# -_-.net
KiCad netlist of a schematic drawn in Altium Designer
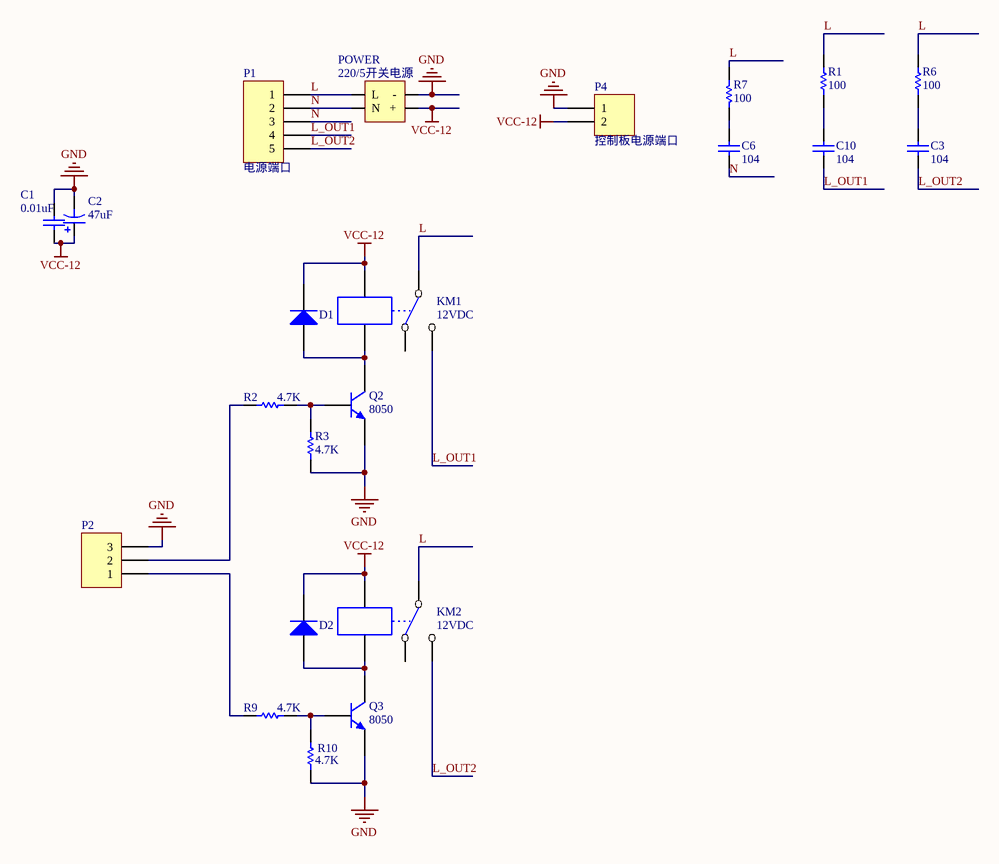
[diagram p0: 智能家居-窗帘-电力板.SchDoc]

(export (version "E")
  (design (tool "Eeschema 10.0.6"))
  (components
    (comp (ref "C1")
      (value "0.01uF")
      (footprint "0.1UF")
      (description "Capacitor")
      (fields (field (name "PUBLISHER") "Altium Limited"))
      (libsource (lib "Miscellaneous Devices") (part "Cap"))
    )
    (comp (ref "C2")
      (value "47uF")
      (footprint "CD5")
      (description "Polarized Capacitor (Radial)")
      (fields (field (name "Comment") "Cap Pol1") (field (name "PUBLISHER") "Altium Limited"))
      (libsource (lib "Miscellaneous Devices") (part "Cap Pol1"))
    )
    (comp (ref "C3")
      (value "104")
      (footprint "0.1UF/275V")
      (description "Capacitor")
      (fields (field (name "Comment") "Cap") (field (name "PUBLISHER") "Altium Limited"))
      (libsource (lib "Miscellaneous Devices") (part "Cap"))
    )
    (comp (ref "C6")
      (value "104")
      (footprint "0.1UF/275V")
      (description "Capacitor")
      (fields (field (name "Comment") "Cap") (field (name "PUBLISHER") "Altium Limited"))
      (libsource (lib "Miscellaneous Devices") (part "Cap"))
    )
    (comp (ref "C10")
      (value "104")
      (footprint "0.1UF/275V")
      (description "Capacitor")
      (fields (field (name "Comment") "Cap") (field (name "PUBLISHER") "Altium Limited"))
      (libsource (lib "Miscellaneous Devices") (part "Cap"))
    )
    (comp (ref "D1")
      (value "Diode")
      (footprint "DIODE")
      (description "Default Diode")
      (fields (field (name "PUBLISHER") "Altium Limited"))
      (libsource (lib "Miscellaneous Devices") (part "Diode"))
    )
    (comp (ref "D2")
      (value "Diode")
      (footprint "DIODE")
      (description "Default Diode")
      (fields (field (name "PUBLISHER") "Altium Limited"))
      (libsource (lib "Miscellaneous Devices") (part "Diode"))
    )
    (comp (ref "KM1") (value "12VDC") (footprint "SRD_RELAY") (libsource (lib "杂项库") (part "SRD-12VDC")))
    (comp (ref "KM2") (value "12VDC") (footprint "SRD_RELAY") (libsource (lib "杂项库") (part "SRD-12VDC")))
    (comp (ref "P1")
      (value "电源端口")
      (footprint "JK128-500-5P")
      (description "Header, 5-Pin")
      (fields (field (name "PUBLISHER") "Altium Limited"))
      (libsource (lib "Miscellaneous Connectors") (part "Header 5"))
    )
    (comp (ref "P2")
      (value "Header 3")
      (footprint "TJC3-3A")
      (description "Header, 3-Pin")
      (fields (field (name "PUBLISHER") "Altium Limited"))
      (libsource (lib "Miscellaneous Connectors") (part "Header 3"))
    )
    (comp (ref "P4")
      (value "控制板电源端口")
      (footprint "TJC3-2A")
      (description "Header, 2-Pin")
      (fields (field (name "PUBLISHER") "Altium Limited"))
      (libsource (lib "Miscellaneous Connectors") (part "Header 2"))
    )
    (comp (ref "POWER")
      (value "220/5开关电源")
      (footprint "220/5开关电源")
      (libsource (lib "杂元件库") (part "220/5开关电源"))
    )
    (comp (ref "Q2")
      (value "8050")
      (footprint "TO-92D")
      (description "NPN Bipolar Transistor")
      (fields (field (name "PUBLISHER") "Altium Limited"))
      (libsource (lib "Miscellaneous Devices") (part "NPN"))
    )
    (comp (ref "Q3")
      (value "8050")
      (footprint "TO-92D")
      (description "NPN Bipolar Transistor")
      (fields (field (name "PUBLISHER") "Altium Limited"))
      (libsource (lib "Miscellaneous Devices") (part "NPN"))
    )
    (comp (ref "R1")
      (value "100")
      (description "Resistor")
      (fields (field (name "PUBLISHER") "Altium Limited"))
      (libsource (lib "Miscellaneous Devices") (part "Res1"))
    )
    (comp (ref "R2")
      (value "4.7K")
      (description "Resistor")
      (fields (field (name "PUBLISHER") "Altium Limited"))
      (libsource (lib "Miscellaneous Devices") (part "Res1"))
    )
    (comp (ref "R3")
      (value "4.7K")
      (description "Resistor")
      (fields (field (name "PUBLISHER") "Altium Limited"))
      (libsource (lib "Miscellaneous Devices") (part "Res1"))
    )
    (comp (ref "R6")
      (value "100")
      (description "Resistor")
      (fields (field (name "PUBLISHER") "Altium Limited"))
      (libsource (lib "Miscellaneous Devices") (part "Res1"))
    )
    (comp (ref "R7")
      (value "100")
      (description "Resistor")
      (fields (field (name "PUBLISHER") "Altium Limited"))
      (libsource (lib "Miscellaneous Devices") (part "Res1"))
    )
    (comp (ref "R9")
      (value "4.7K")
      (description "Resistor")
      (fields (field (name "PUBLISHER") "Altium Limited"))
      (libsource (lib "Miscellaneous Devices") (part "Res1"))
    )
    (comp (ref "R10")
      (value "4.7K")
      (description "Resistor")
      (fields (field (name "PUBLISHER") "Altium Limited"))
      (libsource (lib "Miscellaneous Devices") (part "Res1"))
    )
  )
  (nets
    (net (code "1") (name "/L") (class "Default")
      (node (ref "KM1") (pin "5") (pinfunction "COM_5") (pintype "passive"))
      (node (ref "KM2") (pin "5") (pinfunction "COM_5") (pintype "passive"))
      (node (ref "P1") (pin "1") (pinfunction "1_1") (pintype "passive"))
      (node (ref "POWER") (pin "1") (pinfunction "L_1") (pintype "power_in"))
      (node (ref "R1") (pin "2") (pinfunction "2_2") (pintype "passive"))
      (node (ref "R6") (pin "2") (pinfunction "2_2") (pintype "passive"))
      (node (ref "R7") (pin "1") (pinfunction "1_1") (pintype "passive"))
    )
    (net (code "2") (name "/L_OUT1") (class "Default")
      (node (ref "C10") (pin "1") (pinfunction "1_1") (pintype "passive"))
      (node (ref "KM1") (pin "3") (pinfunction "3_3") (pintype "passive"))
      (node (ref "P1") (pin "4") (pinfunction "4_4") (pintype "passive"))
    )
    (net (code "3") (name "/L_OUT2") (class "Default")
      (node (ref "C3") (pin "1") (pinfunction "1_1") (pintype "passive"))
      (node (ref "KM2") (pin "3") (pinfunction "3_3") (pintype "passive"))
      (node (ref "P1") (pin "5") (pinfunction "5_5") (pintype "passive"))
    )
    (net (code "4") (name "/N") (class "Default")
      (node (ref "C6") (pin "2") (pinfunction "2_2") (pintype "passive"))
      (node (ref "P1") (pin "2") (pinfunction "2_2") (pintype "passive"))
      (node (ref "P1") (pin "3") (pinfunction "3_3") (pintype "passive"))
      (node (ref "POWER") (pin "2") (pinfunction "N_2") (pintype "passive"))
    )
    (net (code "5") (name "GND") (class "Default")
      (node (ref "C1") (pin "2") (pinfunction "2_2") (pintype "passive"))
      (node (ref "C2") (pin "2") (pinfunction "2_2") (pintype "passive"))
      (node (ref "P2") (pin "3") (pinfunction "3_3") (pintype "passive"))
      (node (ref "P4") (pin "1") (pinfunction "1_1") (pintype "passive"))
      (node (ref "POWER") (pin "3") (pinfunction "-_3") (pintype "passive"))
      (node (ref "Q2") (pin "1") (pinfunction "E_1") (pintype "passive"))
      (node (ref "Q3") (pin "1") (pinfunction "E_1") (pintype "passive"))
      (node (ref "R10") (pin "2") (pinfunction "2_2") (pintype "passive"))
      (node (ref "R3") (pin "2") (pinfunction "2_2") (pintype "passive"))
    )
    (net (code "6") (name "Net-(C3-Pad2)") (class "Default")
      (node (ref "C3") (pin "2") (pinfunction "2_2") (pintype "passive"))
      (node (ref "R6") (pin "1") (pinfunction "1_1") (pintype "passive"))
    )
    (net (code "7") (name "Net-(C6-Pad1)") (class "Default")
      (node (ref "C6") (pin "1") (pinfunction "1_1") (pintype "passive"))
      (node (ref "R7") (pin "2") (pinfunction "2_2") (pintype "passive"))
    )
    (net (code "8") (name "Net-(C10-Pad2)") (class "Default")
      (node (ref "C10") (pin "2") (pinfunction "2_2") (pintype "passive"))
      (node (ref "R1") (pin "1") (pinfunction "1_1") (pintype "passive"))
    )
    (net (code "9") (name "Net-(D1-A)") (class "Default")
      (node (ref "D1") (pin "1") (pinfunction "A_1") (pintype "passive"))
      (node (ref "KM1") (pin "4") (pinfunction "4_4") (pintype "passive"))
      (node (ref "Q2") (pin "3") (pinfunction "C_3") (pintype "passive"))
    )
    (net (code "10") (name "Net-(D2-A)") (class "Default")
      (node (ref "D2") (pin "1") (pinfunction "A_1") (pintype "passive"))
      (node (ref "KM2") (pin "4") (pinfunction "4_4") (pintype "passive"))
      (node (ref "Q3") (pin "3") (pinfunction "C_3") (pintype "passive"))
    )
    (net (code "11") (name "Net-(P2-Pad1)") (class "Default")
      (node (ref "P2") (pin "1") (pinfunction "1_1") (pintype "passive"))
      (node (ref "R9") (pin "1") (pinfunction "1_1") (pintype "passive"))
    )
    (net (code "12") (name "Net-(P2-Pad2)") (class "Default")
      (node (ref "P2") (pin "2") (pinfunction "2_2") (pintype "passive"))
      (node (ref "R2") (pin "1") (pinfunction "1_1") (pintype "passive"))
    )
    (net (code "13") (name "Net-(Q2-B)") (class "Default")
      (node (ref "Q2") (pin "2") (pinfunction "B_2") (pintype "passive"))
      (node (ref "R2") (pin "2") (pinfunction "2_2") (pintype "passive"))
      (node (ref "R3") (pin "1") (pinfunction "1_1") (pintype "passive"))
    )
    (net (code "14") (name "Net-(Q3-B)") (class "Default")
      (node (ref "Q3") (pin "2") (pinfunction "B_2") (pintype "passive"))
      (node (ref "R10") (pin "1") (pinfunction "1_1") (pintype "passive"))
      (node (ref "R9") (pin "2") (pinfunction "2_2") (pintype "passive"))
    )
    (net (code "15") (name "VCC-12") (class "Default")
      (node (ref "C1") (pin "1") (pinfunction "1_1") (pintype "passive"))
      (node (ref "C2") (pin "1") (pinfunction "1_1") (pintype "passive"))
      (node (ref "D1") (pin "2") (pinfunction "K_2") (pintype "passive"))
      (node (ref "D2") (pin "2") (pinfunction "K_2") (pintype "passive"))
      (node (ref "KM1") (pin "1") (pinfunction "1_1") (pintype "passive"))
      (node (ref "KM2") (pin "1") (pinfunction "1_1") (pintype "passive"))
      (node (ref "P4") (pin "2") (pinfunction "2_2") (pintype "passive"))
      (node (ref "POWER") (pin "4") (pinfunction "+_4") (pintype "passive"))
    )
    (net (code "16") (name "unconnected-(KM1-Pad2)") (class "Default")
      (node (ref "KM1") (pin "2") (pinfunction "2_2") (pintype "passive"))
    )
    (net (code "17") (name "unconnected-(KM2-Pad2)") (class "Default")
      (node (ref "KM2") (pin "2") (pinfunction "2_2") (pintype "passive"))
    )
  )
)
